# 1clamp_pulse_conv.net
KiCad netlist of a schematic drawn in EAGLE
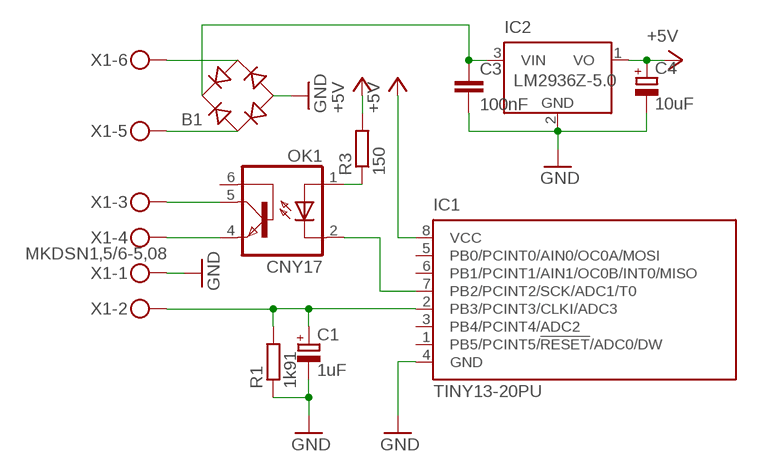
[diagram p0: schematic, sheet 1]

(export (version "E")
  (design (tool "Eeschema 10.0.6"))
  (components
    (comp (ref "B1")
      (value "RB1A")
      (footprint "eagle-import:RB1A")
      (libsource (lib "eagle-import") (part "RB1A"))
    )
    (comp (ref "C1")
      (value "1uF")
      (footprint "eagle-import:E2,5-5")
      (libsource (lib "eagle-import") (part "CPOL-EUE2.5-5"))
    )
    (comp (ref "C3")
      (value "100nF")
      (footprint "eagle-import:C025-025X050")
      (libsource (lib "eagle-import") (part "C-EU025-025X050"))
    )
    (comp (ref "C4")
      (value "10uF")
      (footprint "eagle-import:E2,5-5")
      (libsource (lib "eagle-import") (part "CPOL-EUE2.5-5"))
    )
    (comp (ref "IC1")
      (value "TINY13-20PU")
      (footprint "eagle-import:DIL08")
      (fields (field (name "MPN") "ATTINY13-20PU"))
      (libsource (lib "eagle-import") (part "TINY13PU-20"))
    )
    (comp (ref "IC2")
      (value "LM2936Z-5.0")
      (footprint "eagle-import:TO92")
      (fields (field (name "MF") "NATIONAL SEMICONDUCTOR") (field (name "MPN") "LM2936Z-5.0/NOPB"))
      (libsource (lib "eagle-import") (part "LM2936?Z-5.0"))
    )
    (comp (ref "OK1")
      (value "CNY17")
      (footprint "eagle-import:DIL06")
      (fields (field (name "MPN") "CNY17-1"))
      (libsource (lib "eagle-import") (part "CNY17"))
    )
    (comp (ref "R1")
      (value "1k91")
      (footprint "eagle-import:0204_7")
      (libsource (lib "eagle-import") (part "R-EU_0204/7"))
    )
    (comp (ref "R3")
      (value "150")
      (footprint "eagle-import:0204_7")
      (libsource (lib "eagle-import") (part "R-EU_0204/7"))
    )
    (comp (ref "X1")
      (value "MKDSN1,5/6-5,08")
      (footprint "eagle-import:MKDSN1,5_6-5,08")
      (fields (field (name "MPN") "SMKDSN1,5/6-5,08"))
      (libsource (lib "eagle-import") (part "MKDSN1,5/6-5,08"))
    )
  )
  (nets
    (net (code "1") (name "+5V") (class "Default")
      (node (ref "C4") (pin "+") (pinfunction "+_+") (pintype "passive"))
      (node (ref "IC1") (pin "8") (pinfunction "VCC_8") (pintype "power_in"))
      (node (ref "IC2") (pin "1") (pinfunction "VO_1") (pintype "passive"))
      (node (ref "R3") (pin "2") (pinfunction "2_2") (pintype "passive"))
    )
    (net (code "2") (name "GND") (class "Default")
      (node (ref "B1") (pin "-") (pinfunction "-_-") (pintype "passive"))
      (node (ref "C1") (pin "-") (pinfunction "-_-") (pintype "passive"))
      (node (ref "C3") (pin "2") (pinfunction "2_2") (pintype "passive"))
      (node (ref "C4") (pin "-") (pinfunction "-_-") (pintype "passive"))
      (node (ref "IC1") (pin "4") (pinfunction "GND_4") (pintype "power_in"))
      (node (ref "IC2") (pin "2") (pinfunction "GND_2") (pintype "passive"))
      (node (ref "R1") (pin "1") (pinfunction "1_1") (pintype "passive"))
      (node (ref "X1") (pin "1") (pinfunction "KL_1") (pintype "passive"))
    )
    (net (code "3") (name "Net-(IC1-PB2{slash}PCINT2{slash}SCK{slash}ADC1{slash}T0)") (class "Default")
      (node (ref "IC1") (pin "7") (pinfunction "PB2/PCINT2/SCK/ADC1/T0_7") (pintype "bidirectional"))
      (node (ref "OK1") (pin "2") (pinfunction "C_2") (pintype "passive"))
    )
    (net (code "4") (name "Net-(IC1-PB3{slash}PCINT3{slash}CLKI{slash}ADC3)") (class "Default")
      (node (ref "C1") (pin "+") (pinfunction "+_+") (pintype "passive"))
      (node (ref "IC1") (pin "2") (pinfunction "PB3/PCINT3/CLKI/ADC3_2") (pintype "bidirectional"))
      (node (ref "R1") (pin "2") (pinfunction "2_2") (pintype "passive"))
      (node (ref "X1") (pin "2") (pinfunction "KL_2") (pintype "passive"))
    )
    (net (code "5") (name "Net-(IC2-VIN)") (class "Default")
      (node (ref "B1") (pin "+") (pinfunction "+_+") (pintype "passive"))
      (node (ref "C3") (pin "1") (pinfunction "1_1") (pintype "passive"))
      (node (ref "IC2") (pin "3") (pinfunction "VIN_3") (pintype "input"))
    )
    (net (code "6") (name "Net-(OK1-A)") (class "Default")
      (node (ref "OK1") (pin "1") (pinfunction "A_1") (pintype "passive"))
      (node (ref "R3") (pin "1") (pinfunction "1_1") (pintype "passive"))
    )
    (net (code "7") (name "Net-(OK1-COL)") (class "Default")
      (node (ref "OK1") (pin "5") (pinfunction "COL_5") (pintype "passive"))
      (node (ref "X1") (pin "3") (pinfunction "KL_3") (pintype "passive"))
    )
    (net (code "8") (name "Net-(OK1-EMI)") (class "Default")
      (node (ref "OK1") (pin "4") (pinfunction "EMI_4") (pintype "passive"))
      (node (ref "X1") (pin "4") (pinfunction "KL_4") (pintype "passive"))
    )
    (net (code "9") (name "Net-(X1E-KL)") (class "Default")
      (node (ref "B1") (pin "AC1") (pinfunction "AC1_AC1") (pintype "passive"))
      (node (ref "X1") (pin "5") (pinfunction "KL_5") (pintype "passive"))
    )
    (net (code "10") (name "Net-(X1F-KL)") (class "Default")
      (node (ref "B1") (pin "AC2") (pinfunction "AC2_AC2") (pintype "passive"))
      (node (ref "X1") (pin "6") (pinfunction "KL_6") (pintype "passive"))
    )
    (net (code "11") (name "unconnected-(IC1-PB0{slash}PCINT0{slash}AIN0{slash}OC0A{slash}MOSI-Pad5)") (class "Default")
      (node (ref "IC1") (pin "5") (pinfunction "PB0/PCINT0/AIN0/OC0A/MOSI_5") (pintype "bidirectional"))
    )
    (net (code "12") (name "unconnected-(IC1-PB1{slash}PCINT1{slash}AIN1{slash}OC0B{slash}INT0{slash}MISO-Pad6)") (class "Default")
      (node (ref "IC1") (pin "6") (pinfunction "PB1/PCINT1/AIN1/OC0B/INT0/MISO_6") (pintype "bidirectional"))
    )
    (net (code "13") (name "unconnected-(IC1-PB4{slash}PCINT4{slash}ADC2-Pad3)") (class "Default")
      (node (ref "IC1") (pin "3") (pinfunction "PB4/PCINT4/ADC2_3") (pintype "bidirectional"))
    )
    (net (code "14") (name "unconnected-(IC1-PB5{slash}PCINT5{slash}~{RESET}{slash}ADC0{slash}DW-Pad1)") (class "Default")
      (node (ref "IC1") (pin "1") (pinfunction "PB5/PCINT5/~{RESET}/ADC0/DW_1") (pintype "bidirectional"))
    )
    (net (code "15") (name "unconnected-(OK1-BAS-Pad6)") (class "Default")
      (node (ref "OK1") (pin "6") (pinfunction "BAS_6") (pintype "passive"))
    )
  )
)
